# S65-Shield_v11.net
KiCad netlist of a schematic drawn in EAGLE
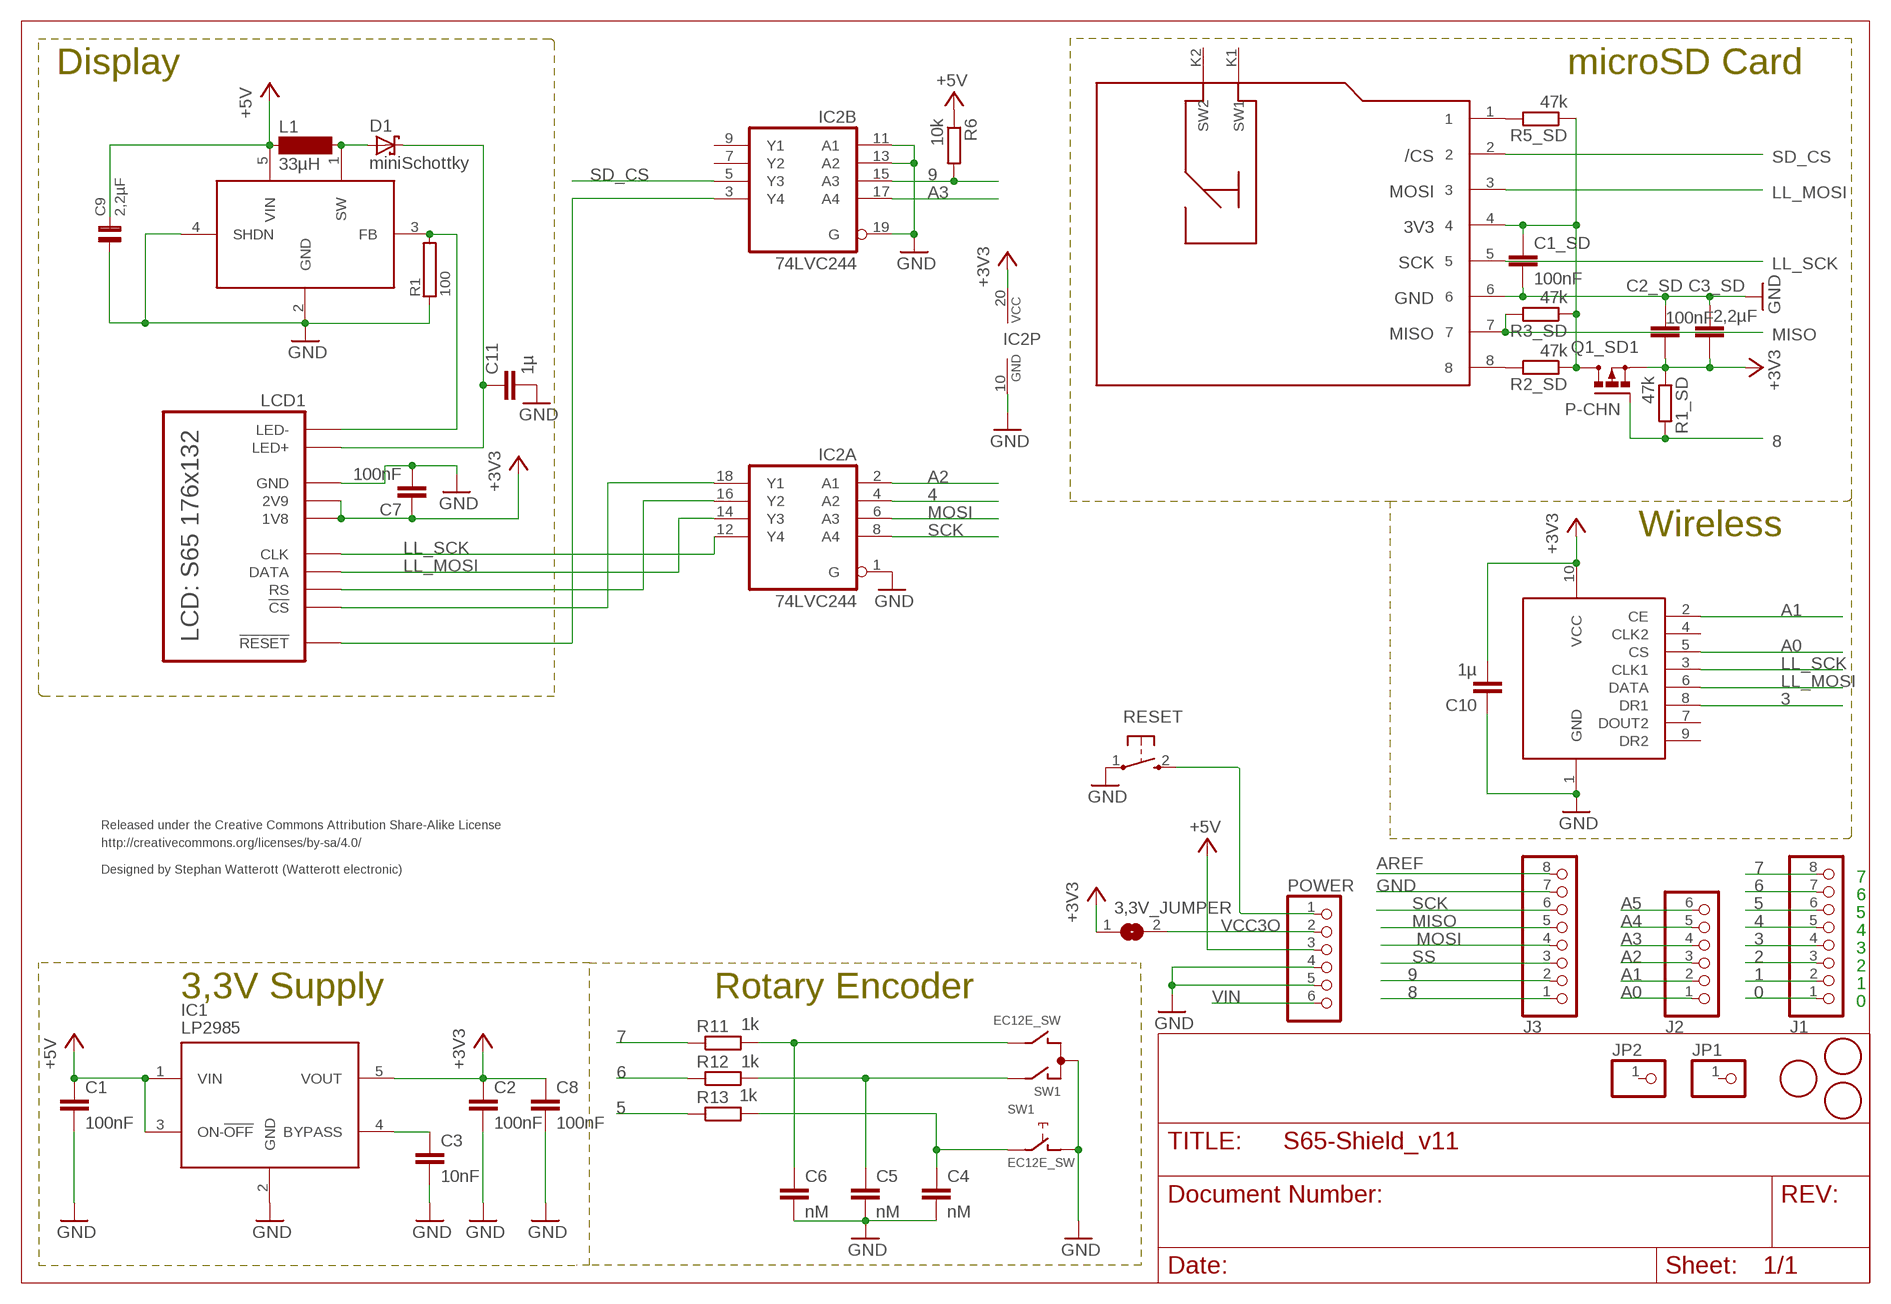
[diagram p0: schematic, sheet 1]

(export (version "E")
  (design (tool "Eeschema 10.0.6"))
  (components
    (comp (ref "3,3V_JUMPER")
      (value "SJ")
      (footprint "eagle-import:SJ")
      (libsource (lib "eagle-import") (part "SJ"))
    )
    (comp (ref "C1")
      (value "100nF")
      (footprint "eagle-import:C0603")
      (libsource (lib "eagle-import") (part "resistor_C-EUC0603"))
    )
    (comp (ref "C1_SD")
      (value "100nF")
      (footprint "eagle-import:C0603")
      (libsource (lib "eagle-import") (part "C-EUC0603"))
    )
    (comp (ref "C2")
      (value "100nF")
      (footprint "eagle-import:C0603")
      (libsource (lib "eagle-import") (part "resistor_C-EUC0603"))
    )
    (comp (ref "C2_SD")
      (value "100nF")
      (footprint "eagle-import:C0603")
      (libsource (lib "eagle-import") (part "C-EUC0603"))
    )
    (comp (ref "C3")
      (value "10nF")
      (footprint "eagle-import:C0603")
      (libsource (lib "eagle-import") (part "resistor_C-EUC0603"))
    )
    (comp (ref "C3_SD")
      (value "2,2µF")
      (footprint "eagle-import:C0805")
      (libsource (lib "eagle-import") (part "C-EUC0805"))
    )
    (comp (ref "C4")
      (value "nM")
      (footprint "eagle-import:C0603")
      (libsource (lib "eagle-import") (part "resistor_C-EUC0603"))
    )
    (comp (ref "C5")
      (value "nM")
      (footprint "eagle-import:C0603")
      (libsource (lib "eagle-import") (part "resistor_C-EUC0603"))
    )
    (comp (ref "C6")
      (value "nM")
      (footprint "eagle-import:C0603")
      (libsource (lib "eagle-import") (part "resistor_C-EUC0603"))
    )
    (comp (ref "C7")
      (value "100nF")
      (footprint "eagle-import:C0603")
      (libsource (lib "eagle-import") (part "resistor_C-EUC0603"))
    )
    (comp (ref "C8")
      (value "100nF")
      (footprint "eagle-import:C0805")
      (libsource (lib "eagle-import") (part "resistor_C-EUC0805"))
    )
    (comp (ref "C9")
      (value "2,2µF")
      (footprint "eagle-import:0805")
      (libsource (lib "eagle-import") (part "CAP0805"))
    )
    (comp (ref "C10")
      (value "1µ")
      (footprint "eagle-import:C0603")
      (libsource (lib "eagle-import") (part "resistor_C-EUC0603"))
    )
    (comp (ref "C11")
      (value "1µ")
      (footprint "eagle-import:C0603")
      (libsource (lib "eagle-import") (part "resistor_C-EUC0603"))
    )
    (comp (ref "D1")
      (value "miniSchottky")
      (footprint "eagle-import:D0603")
      (libsource (lib "eagle-import") (part "DIODE0603"))
    )
    (comp (ref "IC1")
      (value "LP2985")
      (footprint "eagle-import:SOT23-5")
      (libsource (lib "eagle-import") (part "LP2985"))
    )
    (comp (ref "IC2")
      (value "74LVC244")
      (footprint "eagle-import:SO20W")
      (libsource (lib "eagle-import") (part "74244DWAC"))
    )
    (comp (ref "J1")
      (value "PINHD-1X8")
      (footprint "eagle-import:1X08")
      (libsource (lib "eagle-import") (part "PINHD-1X8"))
    )
    (comp (ref "J2")
      (value "PINHD-1X6")
      (footprint "eagle-import:1X06")
      (libsource (lib "eagle-import") (part "PINHD-1X6"))
    )
    (comp (ref "J3")
      (value "PINHD-1X8")
      (footprint "eagle-import:1X08")
      (libsource (lib "eagle-import") (part "PINHD-1X8"))
    )
    (comp (ref "JP1")
      (value "PINHD-1X1")
      (footprint "eagle-import:1X01")
      (libsource (lib "eagle-import") (part "PINHD-1X1"))
    )
    (comp (ref "JP2")
      (value "PINHD-1X1")
      (footprint "eagle-import:1X01")
      (libsource (lib "eagle-import") (part "PINHD-1X1"))
    )
    (comp (ref "L1")
      (value "33µH")
      (footprint "eagle-import:MS42")
      (libsource (lib "eagle-import") (part "MS42"))
    )
    (comp (ref "LCD1")
      (value "S65")
      (footprint "eagle-import:S65")
      (libsource (lib "eagle-import") (part "S65"))
    )
    (comp (ref "POWER")
      (value "PINHD-1X6")
      (footprint "eagle-import:1X06")
      (libsource (lib "eagle-import") (part "PINHD-1X6"))
    )
    (comp (ref "Q1_SD1")
      (value "P-CHN")
      (footprint "eagle-import:MICRO3")
      (libsource (lib "eagle-import") (part "IRLML6402"))
    )
    (comp (ref "R1")
      (value "100")
      (footprint "eagle-import:0603")
      (libsource (lib "eagle-import") (part "R0603"))
    )
    (comp (ref "R1_SD")
      (value "47k")
      (footprint "eagle-import:R0603")
      (libsource (lib "eagle-import") (part "R-EU_R0603"))
    )
    (comp (ref "R2_SD")
      (value "47k")
      (footprint "eagle-import:R0603")
      (libsource (lib "eagle-import") (part "R-EU_R0603"))
    )
    (comp (ref "R3_SD")
      (value "47k")
      (footprint "eagle-import:R0603")
      (libsource (lib "eagle-import") (part "R-EU_R0603"))
    )
    (comp (ref "R5_SD")
      (value "47k")
      (footprint "eagle-import:R0603")
      (libsource (lib "eagle-import") (part "R-EU_R0603"))
    )
    (comp (ref "R6")
      (value "10k")
      (footprint "eagle-import:R0603")
      (libsource (lib "eagle-import") (part "resistor_R-EU_R0603"))
    )
    (comp (ref "R11")
      (value "1k")
      (footprint "eagle-import:R0603")
      (libsource (lib "eagle-import") (part "resistor_R-EU_R0603"))
    )
    (comp (ref "R12")
      (value "1k")
      (footprint "eagle-import:R0603")
      (libsource (lib "eagle-import") (part "resistor_R-EU_R0603"))
    )
    (comp (ref "R13")
      (value "1k")
      (footprint "eagle-import:R0603")
      (libsource (lib "eagle-import") (part "resistor_R-EU_R0603"))
    )
    (comp (ref "RESET")
      (value "TAST_SMD1")
      (footprint "eagle-import:SMD_TASTER")
      (libsource (lib "eagle-import") (part "TAST_SMD1"))
    )
    (comp (ref "SD")
      (value "MICRO-SD")
      (footprint "eagle-import:MICRO-SD")
      (libsource (lib "eagle-import") (part "MICRO-SD"))
    )
    (comp (ref "SW1")
      (value "EC12E_SW")
      (footprint "eagle-import:ALPS_EC12E_SW")
      (libsource (lib "eagle-import") (part "EC12E_SW"))
    )
    (comp (ref "U$1")
      (value "FIDUCIALMOUNT")
      (footprint "eagle-import:FIDUCIA-MOUNT")
      (libsource (lib "eagle-import") (part "FIDUCIALMOUNT"))
    )
    (comp (ref "U$2")
      (value "FIDUCIALMOUNT")
      (footprint "eagle-import:FIDUCIA-MOUNT")
      (libsource (lib "eagle-import") (part "FIDUCIALMOUNT"))
    )
    (comp (ref "U$3")
      (value "FIDUCIALMOUNT")
      (footprint "eagle-import:FIDUCIA-MOUNT")
      (libsource (lib "eagle-import") (part "FIDUCIALMOUNT"))
    )
    (comp (ref "U$4")
      (value "LM2705")
      (footprint "eagle-import:SOT23-5")
      (libsource (lib "eagle-import") (part "LM2705"))
    )
    (comp (ref "U$5")
      (value "TRW-2.4G")
      (footprint "eagle-import:TRW-2.4G")
      (libsource (lib "eagle-import") (part "TRW-2.4G"))
    )
  )
  (nets
    (net (code "1") (name "+3V3") (class "Default")
      (node (ref "3,3V_JUMPER") (pin "1") (pinfunction "1_1") (pintype "passive"))
      (node (ref "C10") (pin "2") (pinfunction "2_2") (pintype "passive"))
      (node (ref "C2") (pin "1") (pinfunction "1_1") (pintype "passive"))
      (node (ref "C2_SD") (pin "2") (pinfunction "2_2") (pintype "passive"))
      (node (ref "C3_SD") (pin "2") (pinfunction "2_2") (pintype "passive"))
      (node (ref "C7") (pin "1") (pinfunction "1_1") (pintype "passive"))
      (node (ref "C8") (pin "1") (pinfunction "1_1") (pintype "passive"))
      (node (ref "IC1") (pin "5") (pinfunction "VOUT_5") (pintype "power_in"))
      (node (ref "IC2") (pin "20") (pinfunction "VCC_20") (pintype "power_in"))
      (node (ref "LCD1") (pin "1V8") (pinfunction "1V8_1V8") (pintype "power_in"))
      (node (ref "LCD1") (pin "2V9") (pinfunction "2V9_2V9") (pintype "power_in"))
      (node (ref "Q1_SD1") (pin "2") (pinfunction "S_2") (pintype "passive"))
      (node (ref "R1_SD") (pin "1") (pinfunction "1_1") (pintype "passive"))
      (node (ref "U$5") (pin "10") (pinfunction "VCC_10") (pintype "bidirectional"))
    )
    (net (code "2") (name "+5V") (class "Default")
      (node (ref "C1") (pin "1") (pinfunction "1_1") (pintype "passive"))
      (node (ref "C9") (pin "2") (pinfunction "2_2") (pintype "passive"))
      (node (ref "IC1") (pin "1") (pinfunction "VIN_1") (pintype "power_in"))
      (node (ref "IC1") (pin "3") (pinfunction "ON-~{OFF}_3") (pintype "input"))
      (node (ref "L1") (pin "1") (pinfunction "1_1") (pintype "passive"))
      (node (ref "POWER") (pin "3") (pinfunction "3_3") (pintype "passive"))
      (node (ref "R6") (pin "1") (pinfunction "1_1") (pintype "passive"))
      (node (ref "U$4") (pin "5") (pinfunction "VIN_5") (pintype "bidirectional"))
    )
    (net (code "3") (name "/0") (class "Default")
      (node (ref "J1") (pin "1") (pinfunction "1_1") (pintype "passive"))
    )
    (net (code "4") (name "/1") (class "Default")
      (node (ref "J1") (pin "2") (pinfunction "2_2") (pintype "passive"))
    )
    (net (code "5") (name "/2") (class "Default")
      (node (ref "J1") (pin "3") (pinfunction "3_3") (pintype "passive"))
    )
    (net (code "6") (name "/3") (class "Default")
      (node (ref "J1") (pin "4") (pinfunction "4_4") (pintype "passive"))
      (node (ref "U$5") (pin "8") (pinfunction "DR1_8") (pintype "bidirectional"))
    )
    (net (code "7") (name "/4") (class "Default")
      (node (ref "IC2") (pin "4") (pinfunction "A2_4") (pintype "input"))
      (node (ref "J1") (pin "5") (pinfunction "5_5") (pintype "passive"))
    )
    (net (code "8") (name "/5") (class "Default")
      (node (ref "J1") (pin "6") (pinfunction "6_6") (pintype "passive"))
      (node (ref "R13") (pin "1") (pinfunction "1_1") (pintype "passive"))
    )
    (net (code "9") (name "/6") (class "Default")
      (node (ref "J1") (pin "7") (pinfunction "7_7") (pintype "passive"))
      (node (ref "R12") (pin "1") (pinfunction "1_1") (pintype "passive"))
    )
    (net (code "10") (name "/7") (class "Default")
      (node (ref "J1") (pin "8") (pinfunction "8_8") (pintype "passive"))
      (node (ref "R11") (pin "1") (pinfunction "1_1") (pintype "passive"))
    )
    (net (code "11") (name "/8") (class "Default")
      (node (ref "J3") (pin "1") (pinfunction "1_1") (pintype "passive"))
      (node (ref "Q1_SD1") (pin "1") (pinfunction "G_1") (pintype "passive"))
      (node (ref "R1_SD") (pin "2") (pinfunction "2_2") (pintype "passive"))
    )
    (net (code "12") (name "/9") (class "Default")
      (node (ref "IC2") (pin "15") (pinfunction "A3_15") (pintype "input"))
      (node (ref "J3") (pin "2") (pinfunction "2_2") (pintype "passive"))
      (node (ref "R6") (pin "2") (pinfunction "2_2") (pintype "passive"))
    )
    (net (code "13") (name "/A0") (class "Default")
      (node (ref "J2") (pin "1") (pinfunction "1_1") (pintype "passive"))
      (node (ref "U$5") (pin "5") (pinfunction "CS_5") (pintype "bidirectional"))
    )
    (net (code "14") (name "/A1") (class "Default")
      (node (ref "J2") (pin "2") (pinfunction "2_2") (pintype "passive"))
      (node (ref "U$5") (pin "2") (pinfunction "CE_2") (pintype "bidirectional"))
    )
    (net (code "15") (name "/A2") (class "Default")
      (node (ref "IC2") (pin "2") (pinfunction "A1_2") (pintype "input"))
      (node (ref "J2") (pin "3") (pinfunction "3_3") (pintype "passive"))
    )
    (net (code "16") (name "/A3") (class "Default")
      (node (ref "IC2") (pin "17") (pinfunction "A4_17") (pintype "input"))
      (node (ref "J2") (pin "4") (pinfunction "4_4") (pintype "passive"))
    )
    (net (code "17") (name "/A4") (class "Default")
      (node (ref "J2") (pin "5") (pinfunction "5_5") (pintype "passive"))
    )
    (net (code "18") (name "/A5") (class "Default")
      (node (ref "J2") (pin "6") (pinfunction "6_6") (pintype "passive"))
    )
    (net (code "19") (name "/AREF") (class "Default")
      (node (ref "J3") (pin "8") (pinfunction "8_8") (pintype "passive"))
    )
    (net (code "20") (name "/LL_MOSI") (class "Default")
      (node (ref "IC2") (pin "14") (pinfunction "Y3_14") (pintype "tri_state"))
      (node (ref "LCD1") (pin "DATA") (pinfunction "DATA_DATA") (pintype "bidirectional"))
      (node (ref "SD") (pin "3") (pinfunction "3_3") (pintype "bidirectional"))
      (node (ref "U$5") (pin "6") (pinfunction "DATA_6") (pintype "bidirectional"))
    )
    (net (code "21") (name "/LL_SCK") (class "Default")
      (node (ref "IC2") (pin "12") (pinfunction "Y4_12") (pintype "tri_state"))
      (node (ref "LCD1") (pin "CLK") (pinfunction "CLK_CLK") (pintype "bidirectional"))
      (node (ref "SD") (pin "5") (pinfunction "5_5") (pintype "bidirectional"))
      (node (ref "U$5") (pin "3") (pinfunction "CLK1_3") (pintype "bidirectional"))
    )
    (net (code "22") (name "/MISO") (class "Default")
      (node (ref "J3") (pin "5") (pinfunction "5_5") (pintype "passive"))
      (node (ref "R3_SD") (pin "2") (pinfunction "2_2") (pintype "passive"))
      (node (ref "SD") (pin "7") (pinfunction "7_7") (pintype "bidirectional"))
    )
    (net (code "23") (name "/MOSI") (class "Default")
      (node (ref "IC2") (pin "6") (pinfunction "A3_6") (pintype "input"))
      (node (ref "J3") (pin "4") (pinfunction "4_4") (pintype "passive"))
    )
    (net (code "24") (name "/SCK") (class "Default")
      (node (ref "IC2") (pin "8") (pinfunction "A4_8") (pintype "input"))
      (node (ref "J3") (pin "6") (pinfunction "6_6") (pintype "passive"))
    )
    (net (code "25") (name "/SD_CS") (class "Default")
      (node (ref "IC2") (pin "5") (pinfunction "Y3_5") (pintype "tri_state"))
      (node (ref "SD") (pin "2") (pinfunction "2_2") (pintype "bidirectional"))
    )
    (net (code "26") (name "/SS") (class "Default")
      (node (ref "J3") (pin "3") (pinfunction "3_3") (pintype "passive"))
    )
    (net (code "27") (name "/VCC3O") (class "Default")
      (node (ref "3,3V_JUMPER") (pin "2") (pinfunction "2_2") (pintype "passive"))
      (node (ref "POWER") (pin "2") (pinfunction "2_2") (pintype "passive"))
    )
    (net (code "28") (name "/VIN") (class "Default")
      (node (ref "POWER") (pin "6") (pinfunction "6_6") (pintype "passive"))
    )
    (net (code "29") (name "GND") (class "Default")
      (node (ref "C1") (pin "2") (pinfunction "2_2") (pintype "passive"))
      (node (ref "C10") (pin "1") (pinfunction "1_1") (pintype "passive"))
      (node (ref "C11") (pin "2") (pinfunction "2_2") (pintype "passive"))
      (node (ref "C1_SD") (pin "2") (pinfunction "2_2") (pintype "passive"))
      (node (ref "C2") (pin "2") (pinfunction "2_2") (pintype "passive"))
      (node (ref "C2_SD") (pin "1") (pinfunction "1_1") (pintype "passive"))
      (node (ref "C3") (pin "2") (pinfunction "2_2") (pintype "passive"))
      (node (ref "C3_SD") (pin "1") (pinfunction "1_1") (pintype "passive"))
      (node (ref "C4") (pin "2") (pinfunction "2_2") (pintype "passive"))
      (node (ref "C5") (pin "2") (pinfunction "2_2") (pintype "passive"))
      (node (ref "C6") (pin "2") (pinfunction "2_2") (pintype "passive"))
      (node (ref "C7") (pin "2") (pinfunction "2_2") (pintype "passive"))
      (node (ref "C8") (pin "2") (pinfunction "2_2") (pintype "passive"))
      (node (ref "C9") (pin "1") (pinfunction "1_1") (pintype "passive"))
      (node (ref "IC1") (pin "2") (pinfunction "GND_2") (pintype "power_in"))
      (node (ref "IC2") (pin "1") (pinfunction "G_1") (pintype "input"))
      (node (ref "IC2") (pin "10") (pinfunction "GND_10") (pintype "power_in"))
      (node (ref "IC2") (pin "11") (pinfunction "A1_11") (pintype "input"))
      (node (ref "IC2") (pin "13") (pinfunction "A2_13") (pintype "input"))
      (node (ref "IC2") (pin "19") (pinfunction "G_19") (pintype "input"))
      (node (ref "J3") (pin "7") (pinfunction "7_7") (pintype "passive"))
      (node (ref "LCD1") (pin "GND") (pinfunction "GND_GND") (pintype "power_in"))
      (node (ref "POWER") (pin "4") (pinfunction "4_4") (pintype "passive"))
      (node (ref "POWER") (pin "5") (pinfunction "5_5") (pintype "passive"))
      (node (ref "R1") (pin "1") (pinfunction "1_1") (pintype "passive"))
      (node (ref "RESET") (pin "1") (pinfunction "P_1") (pintype "passive"))
      (node (ref "SD") (pin "6") (pinfunction "6_6") (pintype "bidirectional"))
      (node (ref "SW1") (pin "C") (pinfunction "C_C") (pintype "passive"))
      (node (ref "SW1") (pin "D") (pinfunction "1_D") (pintype "passive"))
      (node (ref "U$4") (pin "2") (pinfunction "GND_2") (pintype "bidirectional"))
      (node (ref "U$4") (pin "4") (pinfunction "SHDN_4") (pintype "bidirectional"))
      (node (ref "U$5") (pin "1") (pinfunction "GND_1") (pintype "bidirectional"))
    )
    (net (code "30") (name "Net-(C5-Pad1)") (class "Default")
      (node (ref "C5") (pin "1") (pinfunction "1_1") (pintype "passive"))
      (node (ref "R12") (pin "2") (pinfunction "2_2") (pintype "passive"))
      (node (ref "SW1") (pin "A") (pinfunction "A_A") (pintype "passive"))
    )
    (net (code "31") (name "Net-(C6-Pad1)") (class "Default")
      (node (ref "C6") (pin "1") (pinfunction "1_1") (pintype "passive"))
      (node (ref "R11") (pin "2") (pinfunction "2_2") (pintype "passive"))
      (node (ref "SW1") (pin "B") (pinfunction "B_B") (pintype "passive"))
    )
    (net (code "32") (name "Net-(D1-A)") (class "Default")
      (node (ref "D1") (pin "2") (pinfunction "A_2") (pintype "passive"))
      (node (ref "L1") (pin "2") (pinfunction "2_2") (pintype "passive"))
      (node (ref "U$4") (pin "1") (pinfunction "SW_1") (pintype "bidirectional"))
    )
    (net (code "33") (name "Net-(D1-C)") (class "Default")
      (node (ref "C11") (pin "1") (pinfunction "1_1") (pintype "passive"))
      (node (ref "D1") (pin "1") (pinfunction "C_1") (pintype "passive"))
      (node (ref "LCD1") (pin "LED+") (pinfunction "LED+_LED+") (pintype "power_in"))
    )
    (net (code "34") (name "Net-(IC1-BYPASS)") (class "Default")
      (node (ref "C3") (pin "1") (pinfunction "1_1") (pintype "passive"))
      (node (ref "IC1") (pin "4") (pinfunction "BYPASS_4") (pintype "input"))
    )
    (net (code "35") (name "Net-(IC2A-Y1)") (class "Default")
      (node (ref "IC2") (pin "18") (pinfunction "Y1_18") (pintype "tri_state"))
      (node (ref "LCD1") (pin "CS") (pinfunction "~{CS}_CS") (pintype "bidirectional"))
    )
    (net (code "36") (name "Net-(IC2A-Y2)") (class "Default")
      (node (ref "IC2") (pin "16") (pinfunction "Y2_16") (pintype "tri_state"))
      (node (ref "LCD1") (pin "RS") (pinfunction "RS_RS") (pintype "bidirectional"))
    )
    (net (code "37") (name "Net-(IC2B-Y4)") (class "Default")
      (node (ref "IC2") (pin "3") (pinfunction "Y4_3") (pintype "tri_state"))
      (node (ref "LCD1") (pin "RESET") (pinfunction "~{RESET}_RESET") (pintype "bidirectional"))
    )
    (net (code "38") (name "Net-(Q1_SD1-D)") (class "Default")
      (node (ref "C1_SD") (pin "1") (pinfunction "1_1") (pintype "passive"))
      (node (ref "Q1_SD1") (pin "3") (pinfunction "D_3") (pintype "passive"))
      (node (ref "R2_SD") (pin "1") (pinfunction "1_1") (pintype "passive"))
      (node (ref "R3_SD") (pin "1") (pinfunction "1_1") (pintype "passive"))
      (node (ref "R5_SD") (pin "1") (pinfunction "1_1") (pintype "passive"))
      (node (ref "SD") (pin "4") (pinfunction "4_4") (pintype "bidirectional"))
    )
    (net (code "39") (name "Net-(R2_SD-Pad2)") (class "Default")
      (node (ref "R2_SD") (pin "2") (pinfunction "2_2") (pintype "passive"))
      (node (ref "SD") (pin "8") (pinfunction "8_8") (pintype "bidirectional"))
    )
    (net (code "40") (name "Net-(R5_SD-Pad2)") (class "Default")
      (node (ref "R5_SD") (pin "2") (pinfunction "2_2") (pintype "passive"))
      (node (ref "SD") (pin "1") (pinfunction "1_1") (pintype "bidirectional"))
    )
    (net (code "41") (name "Net-(RESET-S)") (class "Default")
      (node (ref "POWER") (pin "1") (pinfunction "1_1") (pintype "passive"))
      (node (ref "RESET") (pin "2") (pinfunction "S_2") (pintype "passive"))
    )
    (net (code "42") (name "Net-(SW1B-2)") (class "Default")
      (node (ref "C4") (pin "1") (pinfunction "1_1") (pintype "passive"))
      (node (ref "R13") (pin "2") (pinfunction "2_2") (pintype "passive"))
      (node (ref "SW1") (pin "E") (pinfunction "2_E") (pintype "passive"))
    )
    (net (code "43") (name "Net-(U$4-FB)") (class "Default")
      (node (ref "LCD1") (pin "LED-") (pinfunction "LED-_LED-") (pintype "power_in"))
      (node (ref "R1") (pin "2") (pinfunction "2_2") (pintype "passive"))
      (node (ref "U$4") (pin "3") (pinfunction "FB_3") (pintype "bidirectional"))
    )
    (net (code "44") (name "unconnected-(IC2B-Y1-Pad9)") (class "Default")
      (node (ref "IC2") (pin "9") (pinfunction "Y1_9") (pintype "tri_state"))
    )
    (net (code "45") (name "unconnected-(IC2B-Y2-Pad7)") (class "Default")
      (node (ref "IC2") (pin "7") (pinfunction "Y2_7") (pintype "tri_state"))
    )
    (net (code "46") (name "unconnected-(JP1-Pad1)") (class "Default")
      (node (ref "JP1") (pin "1") (pinfunction "1_1") (pintype "passive"))
    )
    (net (code "47") (name "unconnected-(JP2-Pad1)") (class "Default")
      (node (ref "JP2") (pin "1") (pinfunction "1_1") (pintype "passive"))
    )
    (net (code "48") (name "unconnected-(SD-SW1-PadK1)") (class "Default")
      (node (ref "SD") (pin "K1") (pinfunction "SW1_K1") (pintype "bidirectional"))
    )
    (net (code "49") (name "unconnected-(SD-SW2-PadK2)") (class "Default")
      (node (ref "SD") (pin "K2") (pinfunction "SW2_K2") (pintype "bidirectional"))
    )
    (net (code "50") (name "unconnected-(U$5-CLK2-Pad4)") (class "Default")
      (node (ref "U$5") (pin "4") (pinfunction "CLK2_4") (pintype "bidirectional"))
    )
    (net (code "51") (name "unconnected-(U$5-DOUT2-Pad7)") (class "Default")
      (node (ref "U$5") (pin "7") (pinfunction "DOUT2_7") (pintype "bidirectional"))
    )
    (net (code "52") (name "unconnected-(U$5-DR2-Pad9)") (class "Default")
      (node (ref "U$5") (pin "9") (pinfunction "DR2_9") (pintype "bidirectional"))
    )
  )
)
